# Interface.net
KiCad netlist of a schematic drawn in Altium Designer
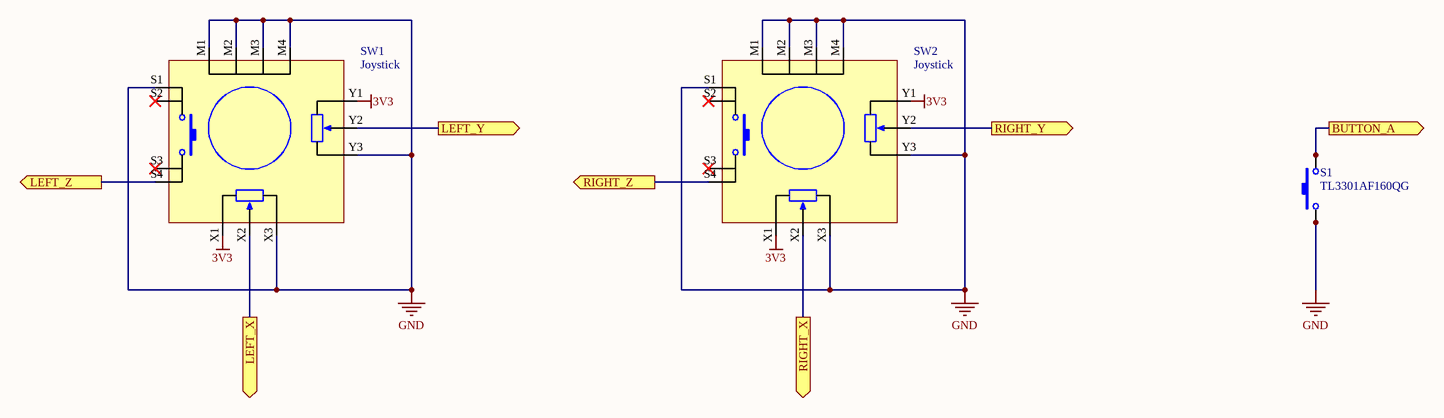
[diagram p0: Interface.SchDoc]

(export (version "E")
  (design (tool "Eeschema 10.0.6"))
  (components
    (comp (ref "S1")
      (value "TL3301AF160QG")
      (footprint "SW_TL3301AFXXXXG")
      (description "SWITCH TACT 160GF H=5.0MM SMT")
      (fields (field (name "MANUFACTURER") "E-Switch"))
      (libsource (lib "library") (part "SW_SPST_2"))
    )
    (comp (ref "SW1") (value "Joystick") (footprint "Joystick") (libsource (lib "Bobbie") (part "Joystick")))
    (comp (ref "SW2") (value "Joystick") (footprint "Joystick") (libsource (lib "Bobbie") (part "Joystick")))
  )
  (nets
    (net (code "1") (name "/BUTTON_A") (class "Default")
      (node (ref "S1") (pin "3") (pinfunction "3_3") (pintype "passive"))
      (node (ref "S1") (pin "4") (pinfunction "4_4") (pintype "passive"))
    )
    (net (code "2") (name "/LEFT_X") (class "Default")
      (node (ref "SW1") (pin "X2") (pinfunction "X2_X2") (pintype "passive"))
    )
    (net (code "3") (name "/LEFT_Y") (class "Default")
      (node (ref "SW1") (pin "Y2") (pinfunction "Y2_Y2") (pintype "passive"))
    )
    (net (code "4") (name "/LEFT_Z") (class "Default")
      (node (ref "SW1") (pin "S4") (pinfunction "S4_S4") (pintype "passive"))
    )
    (net (code "5") (name "/RIGHT_X") (class "Default")
      (node (ref "SW2") (pin "X2") (pinfunction "X2_X2") (pintype "passive"))
    )
    (net (code "6") (name "/RIGHT_Y") (class "Default")
      (node (ref "SW2") (pin "Y2") (pinfunction "Y2_Y2") (pintype "passive"))
    )
    (net (code "7") (name "/RIGHT_Z") (class "Default")
      (node (ref "SW2") (pin "S4") (pinfunction "S4_S4") (pintype "passive"))
    )
    (net (code "8") (name "3V3") (class "Default")
      (node (ref "SW1") (pin "X1") (pinfunction "X1_X1") (pintype "passive"))
      (node (ref "SW1") (pin "Y1") (pinfunction "Y1_Y1") (pintype "passive"))
      (node (ref "SW2") (pin "X1") (pinfunction "X1_X1") (pintype "passive"))
      (node (ref "SW2") (pin "Y1") (pinfunction "Y1_Y1") (pintype "passive"))
    )
    (net (code "9") (name "GND") (class "Default")
      (node (ref "S1") (pin "1") (pinfunction "1_1") (pintype "passive"))
      (node (ref "S1") (pin "2") (pinfunction "2_2") (pintype "passive"))
      (node (ref "SW1") (pin "M1") (pinfunction "M1_M1") (pintype "passive"))
      (node (ref "SW1") (pin "M2") (pinfunction "M2_M2") (pintype "passive"))
      (node (ref "SW1") (pin "M3") (pinfunction "M3_M3") (pintype "passive"))
      (node (ref "SW1") (pin "M4") (pinfunction "M4_M4") (pintype "passive"))
      (node (ref "SW1") (pin "S1") (pinfunction "S1_S1") (pintype "passive"))
      (node (ref "SW1") (pin "X3") (pinfunction "X3_X3") (pintype "passive"))
      (node (ref "SW1") (pin "Y3") (pinfunction "Y3_Y3") (pintype "passive"))
      (node (ref "SW2") (pin "M1") (pinfunction "M1_M1") (pintype "passive"))
      (node (ref "SW2") (pin "M2") (pinfunction "M2_M2") (pintype "passive"))
      (node (ref "SW2") (pin "M3") (pinfunction "M3_M3") (pintype "passive"))
      (node (ref "SW2") (pin "M4") (pinfunction "M4_M4") (pintype "passive"))
      (node (ref "SW2") (pin "S1") (pinfunction "S1_S1") (pintype "passive"))
      (node (ref "SW2") (pin "X3") (pinfunction "X3_X3") (pintype "passive"))
      (node (ref "SW2") (pin "Y3") (pinfunction "Y3_Y3") (pintype "passive"))
    )
    (net (code "10") (name "unconnected-(SW1-PadS2)") (class "Default")
      (node (ref "SW1") (pin "S2") (pinfunction "S2_S2") (pintype "passive+no_connect"))
    )
    (net (code "11") (name "unconnected-(SW1-PadS3)") (class "Default")
      (node (ref "SW1") (pin "S3") (pinfunction "S3_S3") (pintype "passive+no_connect"))
    )
    (net (code "12") (name "unconnected-(SW2-PadS2)") (class "Default")
      (node (ref "SW2") (pin "S2") (pinfunction "S2_S2") (pintype "passive+no_connect"))
    )
    (net (code "13") (name "unconnected-(SW2-PadS3)") (class "Default")
      (node (ref "SW2") (pin "S3") (pinfunction "S3_S3") (pintype "passive+no_connect"))
    )
  )
)
